# node_td.net
KiCad netlist of a schematic drawn in EAGLE
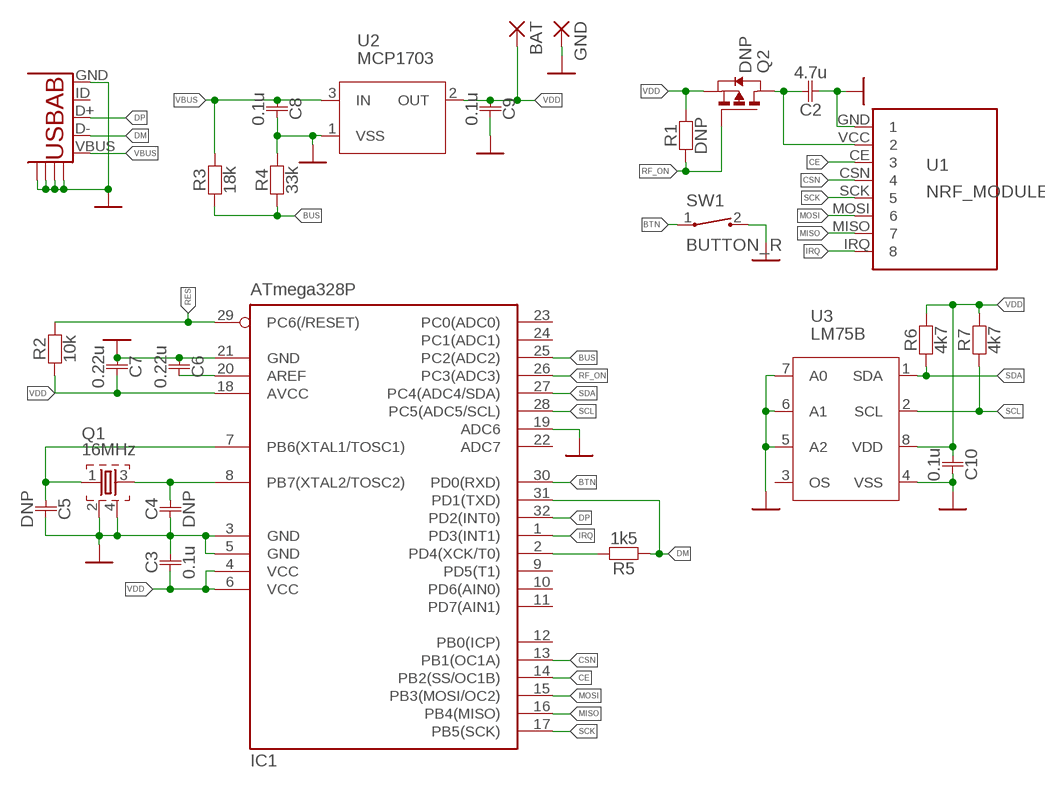
[diagram p0: schematic, sheet 1]

(export (version "E")
  (design (tool "Eeschema 10.0.6"))
  (components
    (comp (ref "BAT")
      (value "WIREPAD1,6/0,9")
      (footprint "eagle-import:1,6_0,9")
      (libsource (lib "eagle-import") (part "WIREPAD1,6/0,9"))
    )
    (comp (ref "C2")
      (value "4.7u")
      (footprint "eagle-import:0805")
      (libsource (lib "eagle-import") (part "C0805"))
    )
    (comp (ref "C3")
      (value "0.1u")
      (footprint "eagle-import:0402")
      (libsource (lib "eagle-import") (part "C0402"))
    )
    (comp (ref "C4")
      (value "DNP")
      (footprint "eagle-import:0402")
      (libsource (lib "eagle-import") (part "C0402"))
    )
    (comp (ref "C5")
      (value "DNP")
      (footprint "eagle-import:0402")
      (libsource (lib "eagle-import") (part "C0402"))
    )
    (comp (ref "C6")
      (value "0.22u")
      (footprint "eagle-import:0402")
      (libsource (lib "eagle-import") (part "C0402"))
    )
    (comp (ref "C7")
      (value "0.22u")
      (footprint "eagle-import:0402")
      (libsource (lib "eagle-import") (part "C0402"))
    )
    (comp (ref "C8")
      (value "0.1u")
      (footprint "eagle-import:0402")
      (libsource (lib "eagle-import") (part "C0402"))
    )
    (comp (ref "C9")
      (value "0.1u")
      (footprint "eagle-import:0402")
      (libsource (lib "eagle-import") (part "C0402"))
    )
    (comp (ref "C10")
      (value "0.1u")
      (footprint "eagle-import:0402")
      (libsource (lib "eagle-import") (part "C0402"))
    )
    (comp (ref "GND")
      (value "WIREPAD1,6/0,9")
      (footprint "eagle-import:1,6_0,9")
      (libsource (lib "eagle-import") (part "WIREPAD1,6/0,9"))
    )
    (comp (ref "IC1")
      (value "ATmega328P")
      (footprint "eagle-import:TQFP32-08")
      (fields (field (name "MPN") "ATMEGA8-16AU"))
      (libsource (lib "eagle-import") (part "MEGA8-AI"))
    )
    (comp (ref "Q1")
      (value "16MHz")
      (footprint "eagle-import:FA-20H")
      (libsource (lib "eagle-import") (part "FA-3225"))
    )
    (comp (ref "Q2")
      (value "DNP")
      (footprint "eagle-import:SOT23")
      (libsource (lib "eagle-import") (part "P-CHANNEL"))
    )
    (comp (ref "R1")
      (value "DNP")
      (footprint "eagle-import:0402")
      (libsource (lib "eagle-import") (part "R0402"))
    )
    (comp (ref "R2")
      (value "10k")
      (footprint "eagle-import:0402")
      (libsource (lib "eagle-import") (part "R0402"))
    )
    (comp (ref "R3")
      (value "18k")
      (footprint "eagle-import:0402")
      (libsource (lib "eagle-import") (part "R0402"))
    )
    (comp (ref "R4")
      (value "33k")
      (footprint "eagle-import:0402")
      (libsource (lib "eagle-import") (part "R0402"))
    )
    (comp (ref "R5")
      (value "1k5")
      (footprint "eagle-import:0402")
      (libsource (lib "eagle-import") (part "R0402"))
    )
    (comp (ref "R6")
      (value "4k7")
      (footprint "eagle-import:0402")
      (libsource (lib "eagle-import") (part "R0402"))
    )
    (comp (ref "R7")
      (value "4k7")
      (footprint "eagle-import:0402")
      (libsource (lib "eagle-import") (part "R0402"))
    )
    (comp (ref "SW1")
      (value "BUTTON_R")
      (footprint "eagle-import:BUTTON_1")
      (libsource (lib "eagle-import") (part "BUTTON_R"))
    )
    (comp (ref "U$1")
      (value "UNTITLED_USB_AB")
      (footprint "eagle-import:USB-MICRO-MOD")
      (libsource (lib "eagle-import") (part "UNTITLED_USB_AB"))
    )
    (comp (ref "U1")
      (value "NRF_MODULE")
      (footprint "eagle-import:NRF_MODULE")
      (libsource (lib "eagle-import") (part "NRF_MODULE"))
    )
    (comp (ref "U2")
      (value "MCP1703")
      (footprint "eagle-import:SOT23")
      (libsource (lib "eagle-import") (part "MCP1703"))
    )
    (comp (ref "U3")
      (value "LM75B")
      (footprint "eagle-import:MSOP8")
      (libsource (lib "eagle-import") (part "LM75DP"))
    )
  )
  (nets
    (net (code "1") (name "BTN") (class "Default")
      (node (ref "IC1") (pin "30") (pinfunction "PD0(RXD)_30") (pintype "bidirectional"))
      (node (ref "SW1") (pin "1") (pinfunction "1_1") (pintype "passive"))
    )
    (net (code "2") (name "BUS") (class "Default")
      (node (ref "IC1") (pin "25") (pinfunction "PC2(ADC2)_25") (pintype "bidirectional"))
      (node (ref "R3") (pin "P$1") (pinfunction "P$1_P$1") (pintype "passive"))
      (node (ref "R4") (pin "P$1") (pinfunction "P$1_P$1") (pintype "passive"))
    )
    (net (code "3") (name "CE") (class "Default")
      (node (ref "IC1") (pin "14") (pinfunction "PB2(SS/OC1B)_14") (pintype "bidirectional"))
      (node (ref "U1") (pin "CE") (pinfunction "3_CE") (pintype "input"))
    )
    (net (code "4") (name "CSN") (class "Default")
      (node (ref "IC1") (pin "13") (pinfunction "PB1(OC1A)_13") (pintype "bidirectional"))
      (node (ref "U1") (pin "CSN") (pinfunction "4_CSN") (pintype "input"))
    )
    (net (code "5") (name "DM") (class "Default")
      (node (ref "IC1") (pin "31") (pinfunction "PD1(TXD)_31") (pintype "bidirectional"))
      (node (ref "R5") (pin "P$1") (pinfunction "P$1_P$1") (pintype "passive"))
      (node (ref "U$1") (pin "D-") (pinfunction "D-_D-") (pintype "bidirectional"))
    )
    (net (code "6") (name "DP") (class "Default")
      (node (ref "IC1") (pin "32") (pinfunction "PD2(INT0)_32") (pintype "bidirectional"))
      (node (ref "U$1") (pin "D+") (pinfunction "D+_D+") (pintype "bidirectional"))
    )
    (net (code "7") (name "GND") (class "Default")
      (node (ref "C10") (pin "P$2") (pinfunction "P$2_P$2") (pintype "passive"))
      (node (ref "C2") (pin "P$1") (pinfunction "P$1_P$1") (pintype "passive"))
      (node (ref "C3") (pin "P$2") (pinfunction "P$2_P$2") (pintype "passive"))
      (node (ref "C4") (pin "P$1") (pinfunction "P$1_P$1") (pintype "passive"))
      (node (ref "C5") (pin "P$2") (pinfunction "P$2_P$2") (pintype "passive"))
      (node (ref "C6") (pin "P$1") (pinfunction "P$1_P$1") (pintype "passive"))
      (node (ref "C7") (pin "P$1") (pinfunction "P$1_P$1") (pintype "passive"))
      (node (ref "C8") (pin "P$2") (pinfunction "P$2_P$2") (pintype "passive"))
      (node (ref "C9") (pin "P$2") (pinfunction "P$2_P$2") (pintype "passive"))
      (node (ref "GND") (pin "1") (pinfunction "P_1") (pintype "passive"))
      (node (ref "IC1") (pin "19") (pinfunction "ADC6_19") (pintype "bidirectional"))
      (node (ref "IC1") (pin "21") (pinfunction "GND_21") (pintype "power_in"))
      (node (ref "IC1") (pin "3") (pinfunction "GND_3") (pintype "power_in"))
      (node (ref "IC1") (pin "5") (pinfunction "GND_5") (pintype "power_in"))
      (node (ref "Q1") (pin "2") (pinfunction "2_2") (pintype "passive"))
      (node (ref "Q1") (pin "4") (pinfunction "4_4") (pintype "passive"))
      (node (ref "R4") (pin "P$2") (pinfunction "P$2_P$2") (pintype "passive"))
      (node (ref "SW1") (pin "2") (pinfunction "2_2") (pintype "passive"))
      (node (ref "U$1") (pin "GND") (pinfunction "GND_GND") (pintype "power_in"))
      (node (ref "U$1") (pin "GND@1") (pinfunction "P$1_GND@1") (pintype "power_in"))
      (node (ref "U$1") (pin "GND@2") (pinfunction "P$2_GND@2") (pintype "power_in"))
      (node (ref "U$1") (pin "GND@3") (pinfunction "P$3_GND@3") (pintype "power_in"))
      (node (ref "U$1") (pin "GND@4") (pinfunction "P$4_GND@4") (pintype "power_in"))
      (node (ref "U1") (pin "GND") (pinfunction "1_GND") (pintype "power_in"))
      (node (ref "U2") (pin "1") (pinfunction "VSS_1") (pintype "power_in"))
      (node (ref "U3") (pin "4") (pinfunction "VSS_4") (pintype "power_in"))
      (node (ref "U3") (pin "5") (pinfunction "A2_5") (pintype "input"))
      (node (ref "U3") (pin "6") (pinfunction "A1_6") (pintype "input"))
      (node (ref "U3") (pin "7") (pinfunction "A0_7") (pintype "input"))
    )
    (net (code "8") (name "IRQ") (class "Default")
      (node (ref "IC1") (pin "1") (pinfunction "PD3(INT1)_1") (pintype "bidirectional"))
      (node (ref "U1") (pin "IRQ") (pinfunction "8_IRQ") (pintype "output"))
    )
    (net (code "9") (name "MISO") (class "Default")
      (node (ref "IC1") (pin "16") (pinfunction "PB4(MISO)_16") (pintype "bidirectional"))
      (node (ref "U1") (pin "MISO") (pinfunction "7_MISO") (pintype "output"))
    )
    (net (code "10") (name "MOSI") (class "Default")
      (node (ref "IC1") (pin "15") (pinfunction "PB3(MOSI/OC2)_15") (pintype "bidirectional"))
      (node (ref "U1") (pin "MOSI") (pinfunction "6_MOSI") (pintype "input"))
    )
    (net (code "11") (name "Net-(IC1-AREF)") (class "Default")
      (node (ref "C6") (pin "P$2") (pinfunction "P$2_P$2") (pintype "passive"))
      (node (ref "IC1") (pin "20") (pinfunction "AREF_20") (pintype "passive"))
    )
    (net (code "12") (name "Net-(IC1-PB6(XTAL1{slash}TOSC1))") (class "Default")
      (node (ref "C5") (pin "P$1") (pinfunction "P$1_P$1") (pintype "passive"))
      (node (ref "IC1") (pin "7") (pinfunction "PB6(XTAL1/TOSC1)_7") (pintype "bidirectional"))
      (node (ref "Q1") (pin "1") (pinfunction "1_1") (pintype "passive"))
    )
    (net (code "13") (name "Net-(IC1-PB7(XTAL2{slash}TOSC2))") (class "Default")
      (node (ref "C4") (pin "P$2") (pinfunction "P$2_P$2") (pintype "passive"))
      (node (ref "IC1") (pin "8") (pinfunction "PB7(XTAL2/TOSC2)_8") (pintype "bidirectional"))
      (node (ref "Q1") (pin "3") (pinfunction "3_3") (pintype "passive"))
    )
    (net (code "14") (name "Net-(IC1-PD4(XCK{slash}T0))") (class "Default")
      (node (ref "IC1") (pin "2") (pinfunction "PD4(XCK/T0)_2") (pintype "bidirectional"))
      (node (ref "R5") (pin "P$2") (pinfunction "P$2_P$2") (pintype "passive"))
    )
    (net (code "15") (name "Net-(Q2-D)") (class "Default")
      (node (ref "C2") (pin "P$2") (pinfunction "P$2_P$2") (pintype "passive"))
      (node (ref "Q2") (pin "3") (pinfunction "D_3") (pintype "passive"))
      (node (ref "U1") (pin "VCC") (pinfunction "2_VCC") (pintype "power_in"))
    )
    (net (code "16") (name "RES") (class "Default")
      (node (ref "IC1") (pin "29") (pinfunction "PC6(/RESET)_29") (pintype "bidirectional"))
      (node (ref "R2") (pin "P$2") (pinfunction "P$2_P$2") (pintype "passive"))
    )
    (net (code "17") (name "RF_ON") (class "Default")
      (node (ref "IC1") (pin "26") (pinfunction "PC3(ADC3)_26") (pintype "bidirectional"))
      (node (ref "Q2") (pin "1") (pinfunction "G_1") (pintype "passive"))
      (node (ref "R1") (pin "P$1") (pinfunction "P$1_P$1") (pintype "passive"))
    )
    (net (code "18") (name "SCK") (class "Default")
      (node (ref "IC1") (pin "17") (pinfunction "PB5(SCK)_17") (pintype "bidirectional"))
      (node (ref "U1") (pin "SCK") (pinfunction "5_SCK") (pintype "input"))
    )
    (net (code "19") (name "SCL") (class "Default")
      (node (ref "IC1") (pin "28") (pinfunction "PC5(ADC5/SCL)_28") (pintype "bidirectional"))
      (node (ref "R7") (pin "P$1") (pinfunction "P$1_P$1") (pintype "passive"))
      (node (ref "U3") (pin "2") (pinfunction "SCL_2") (pintype "bidirectional"))
    )
    (net (code "20") (name "SDA") (class "Default")
      (node (ref "IC1") (pin "27") (pinfunction "PC4(ADC4/SDA)_27") (pintype "bidirectional"))
      (node (ref "R6") (pin "P$1") (pinfunction "P$1_P$1") (pintype "passive"))
      (node (ref "U3") (pin "1") (pinfunction "SDA_1") (pintype "bidirectional"))
    )
    (net (code "21") (name "VBUS") (class "Default")
      (node (ref "C8") (pin "P$1") (pinfunction "P$1_P$1") (pintype "passive"))
      (node (ref "R3") (pin "P$2") (pinfunction "P$2_P$2") (pintype "passive"))
      (node (ref "U$1") (pin "VBUS") (pinfunction "VBUS_VBUS") (pintype "power_in"))
      (node (ref "U2") (pin "3") (pinfunction "IN_3") (pintype "input"))
    )
    (net (code "22") (name "VDD") (class "Default")
      (node (ref "BAT") (pin "1") (pinfunction "P_1") (pintype "passive"))
      (node (ref "C10") (pin "P$1") (pinfunction "P$1_P$1") (pintype "passive"))
      (node (ref "C3") (pin "P$1") (pinfunction "P$1_P$1") (pintype "passive"))
      (node (ref "C7") (pin "P$2") (pinfunction "P$2_P$2") (pintype "passive"))
      (node (ref "C9") (pin "P$1") (pinfunction "P$1_P$1") (pintype "passive"))
      (node (ref "IC1") (pin "18") (pinfunction "AVCC_18") (pintype "power_in"))
      (node (ref "IC1") (pin "4") (pinfunction "VCC_4") (pintype "power_in"))
      (node (ref "IC1") (pin "6") (pinfunction "VCC_6") (pintype "power_in"))
      (node (ref "Q2") (pin "2") (pinfunction "S_2") (pintype "passive"))
      (node (ref "R1") (pin "P$2") (pinfunction "P$2_P$2") (pintype "passive"))
      (node (ref "R2") (pin "P$1") (pinfunction "P$1_P$1") (pintype "passive"))
      (node (ref "R6") (pin "P$2") (pinfunction "P$2_P$2") (pintype "passive"))
      (node (ref "R7") (pin "P$2") (pinfunction "P$2_P$2") (pintype "passive"))
      (node (ref "U2") (pin "2") (pinfunction "OUT_2") (pintype "output"))
      (node (ref "U3") (pin "8") (pinfunction "VDD_8") (pintype "power_in"))
    )
    (net (code "23") (name "unconnected-(IC1-ADC7-Pad22)") (class "Default")
      (node (ref "IC1") (pin "22") (pinfunction "ADC7_22") (pintype "bidirectional"))
    )
    (net (code "24") (name "unconnected-(IC1-PB0(ICP)-Pad12)") (class "Default")
      (node (ref "IC1") (pin "12") (pinfunction "PB0(ICP)_12") (pintype "bidirectional"))
    )
    (net (code "25") (name "unconnected-(IC1-PC0(ADC0)-Pad23)") (class "Default")
      (node (ref "IC1") (pin "23") (pinfunction "PC0(ADC0)_23") (pintype "bidirectional"))
    )
    (net (code "26") (name "unconnected-(IC1-PC1(ADC1)-Pad24)") (class "Default")
      (node (ref "IC1") (pin "24") (pinfunction "PC1(ADC1)_24") (pintype "bidirectional"))
    )
    (net (code "27") (name "unconnected-(IC1-PD5(T1)-Pad9)") (class "Default")
      (node (ref "IC1") (pin "9") (pinfunction "PD5(T1)_9") (pintype "bidirectional"))
    )
    (net (code "28") (name "unconnected-(IC1-PD6(AIN0)-Pad10)") (class "Default")
      (node (ref "IC1") (pin "10") (pinfunction "PD6(AIN0)_10") (pintype "bidirectional"))
    )
    (net (code "29") (name "unconnected-(IC1-PD7(AIN1)-Pad11)") (class "Default")
      (node (ref "IC1") (pin "11") (pinfunction "PD7(AIN1)_11") (pintype "bidirectional"))
    )
    (net (code "30") (name "unconnected-(U$1-USBID-PadID)") (class "Default")
      (node (ref "U$1") (pin "ID") (pinfunction "USBID_ID") (pintype "bidirectional"))
    )
    (net (code "31") (name "unconnected-(U3-OS-Pad3)") (class "Default")
      (node (ref "U3") (pin "3") (pinfunction "OS_3") (pintype "output"))
    )
  )
)
